# Macropad_V1_0.net
KiCad netlist of a schematic drawn in Altium Designer
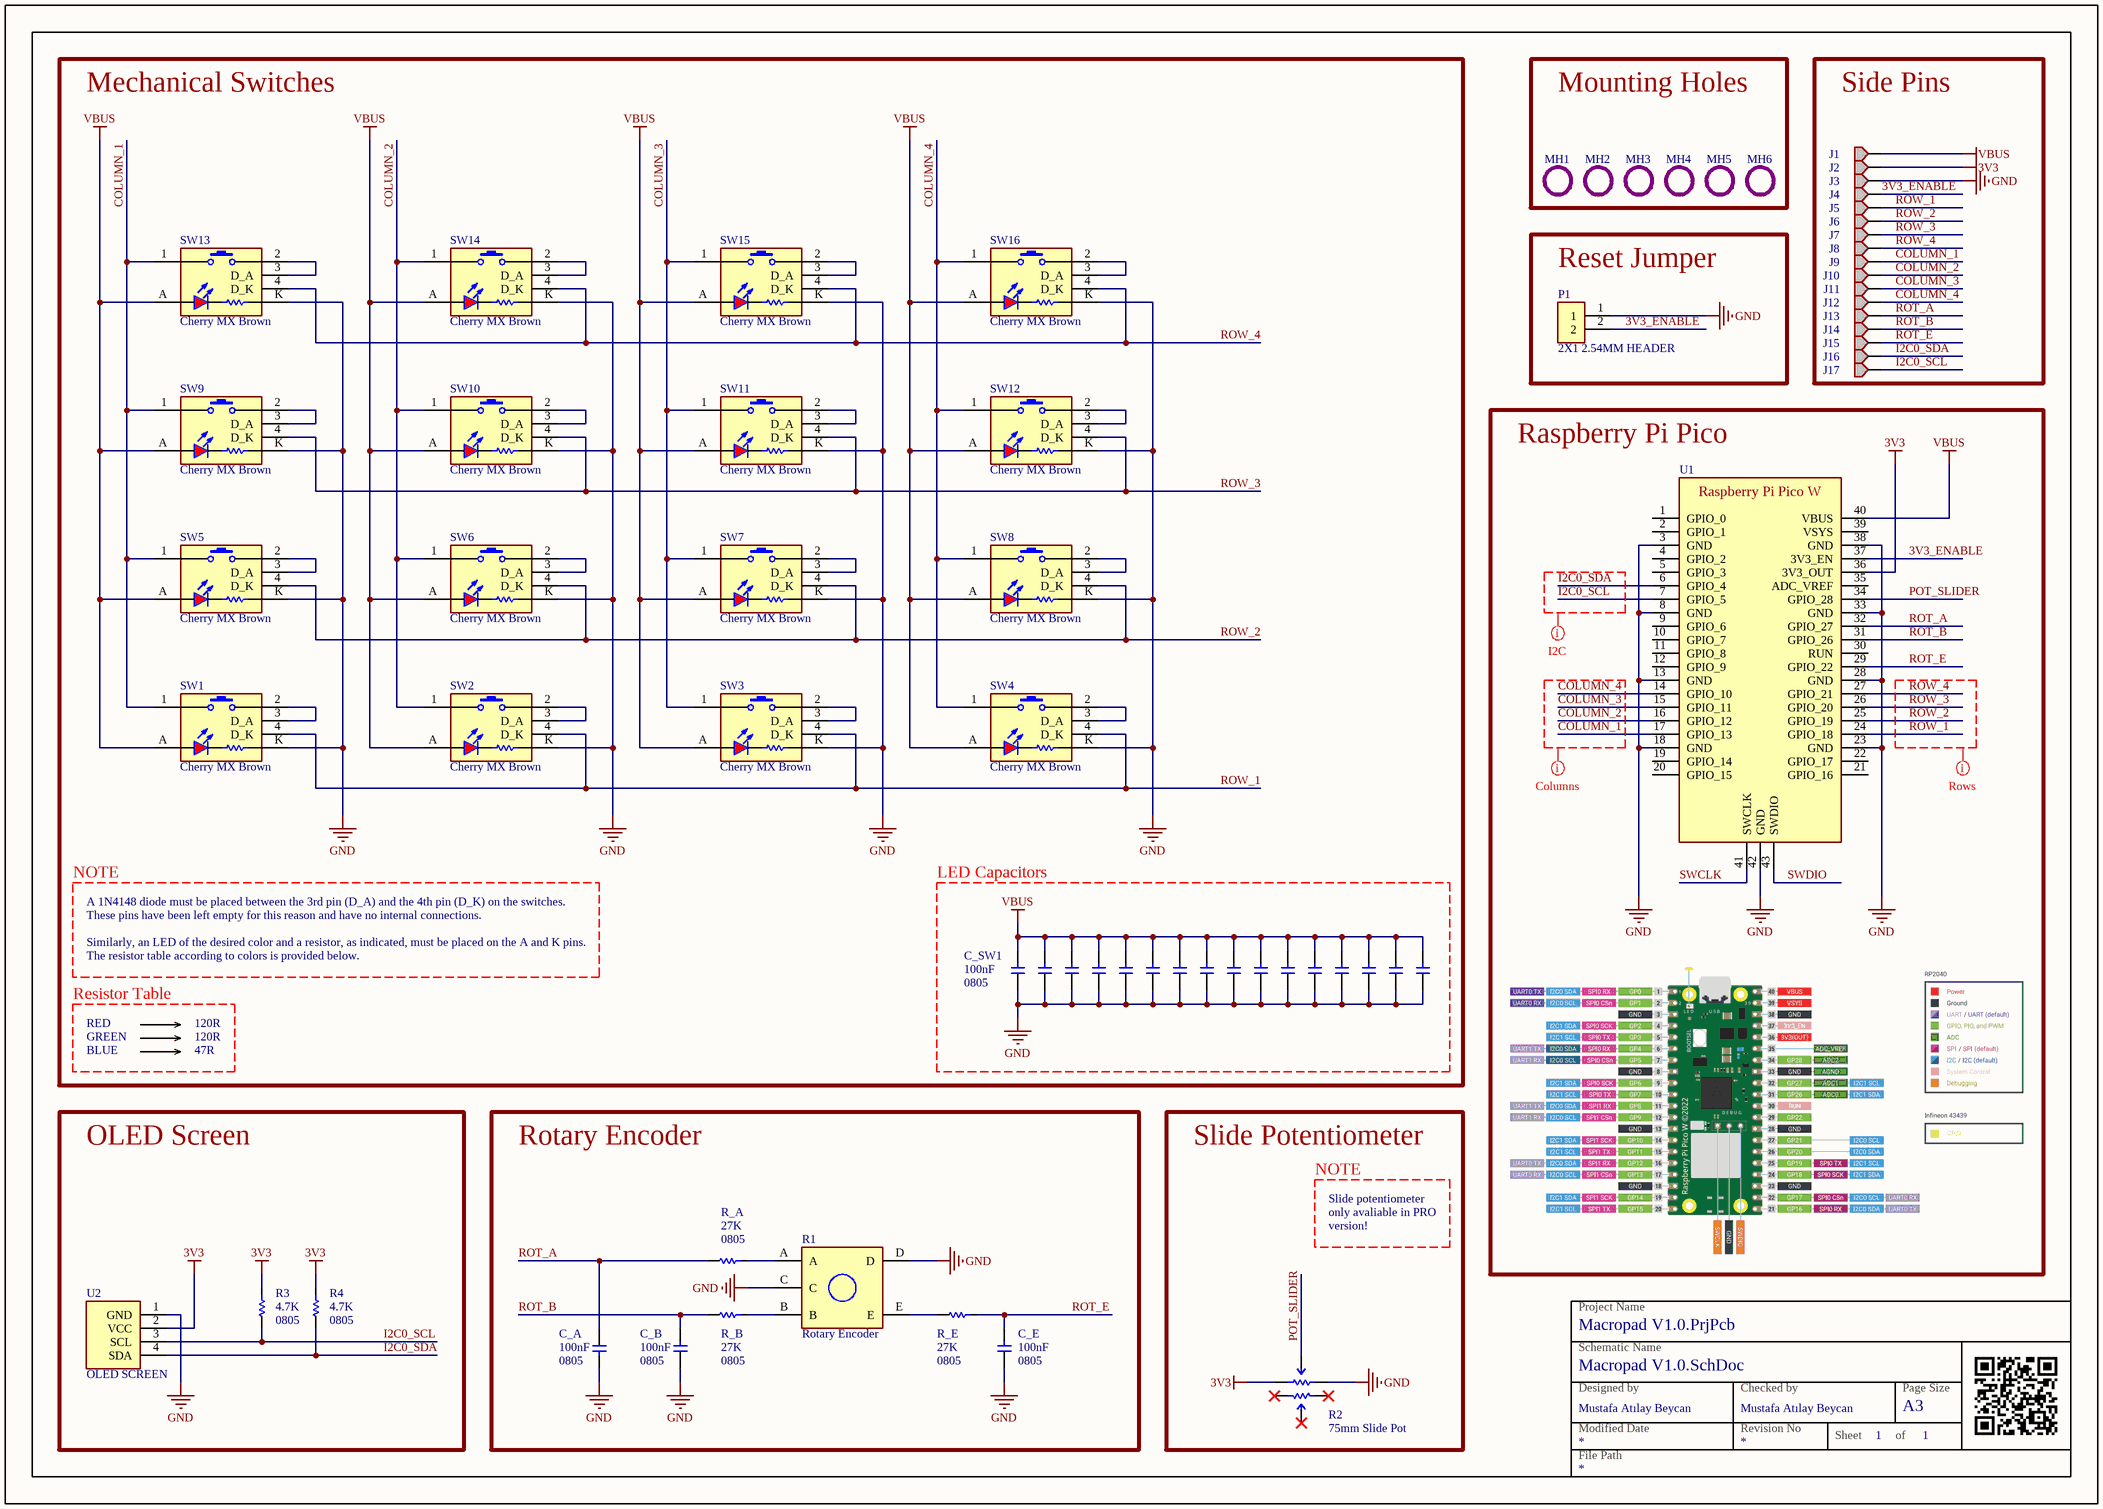
[diagram p0: Macropad V1.0.SchDoc]

(export (version "E")
  (design (tool "Eeschema 10.0.6"))
  (components
    (comp (ref "C_A")
      (value "CAP CER")
      (footprint "CAP 0805")
      (fields (field (name "CAPACITANCE") "100nF") (field (name "PACKAGE") "0805"))
      (libsource (lib "Mustafa Library") (part "CAP CER"))
    )
    (comp (ref "C_B")
      (value "CAP CER")
      (footprint "CAP 0805")
      (fields (field (name "CAPACITANCE") "100nF") (field (name "PACKAGE") "0805"))
      (libsource (lib "Mustafa Library") (part "CAP CER"))
    )
    (comp (ref "C_E")
      (value "CAP CER")
      (footprint "CAP 0805")
      (fields (field (name "CAPACITANCE") "100nF") (field (name "PACKAGE") "0805"))
      (libsource (lib "Mustafa Library") (part "CAP CER"))
    )
    (comp (ref "C_SW1")
      (value "CAP CER")
      (footprint "CAP 0805")
      (fields (field (name "CAPACITANCE") "100nF") (field (name "PACKAGE") "0805"))
      (libsource (lib "Mustafa Library") (part "CAP CER"))
    )
    (comp (ref "C_SW2")
      (value "CAP CER")
      (footprint "CAP 0805")
      (libsource (lib "Mustafa Library") (part "CAP CER"))
    )
    (comp (ref "C_SW3")
      (value "CAP CER")
      (footprint "CAP 0805")
      (libsource (lib "Mustafa Library") (part "CAP CER"))
    )
    (comp (ref "C_SW4")
      (value "CAP CER")
      (footprint "CAP 0805")
      (libsource (lib "Mustafa Library") (part "CAP CER"))
    )
    (comp (ref "C_SW5")
      (value "CAP CER")
      (footprint "CAP 0805")
      (libsource (lib "Mustafa Library") (part "CAP CER"))
    )
    (comp (ref "C_SW6")
      (value "CAP CER")
      (footprint "CAP 0805")
      (libsource (lib "Mustafa Library") (part "CAP CER"))
    )
    (comp (ref "C_SW7")
      (value "CAP CER")
      (footprint "CAP 0805")
      (libsource (lib "Mustafa Library") (part "CAP CER"))
    )
    (comp (ref "C_SW8")
      (value "CAP CER")
      (footprint "CAP 0805")
      (libsource (lib "Mustafa Library") (part "CAP CER"))
    )
    (comp (ref "C_SW9")
      (value "CAP CER")
      (footprint "CAP 0805")
      (libsource (lib "Mustafa Library") (part "CAP CER"))
    )
    (comp (ref "C_SW10")
      (value "CAP CER")
      (footprint "CAP 0805")
      (libsource (lib "Mustafa Library") (part "CAP CER"))
    )
    (comp (ref "C_SW11")
      (value "CAP CER")
      (footprint "CAP 0805")
      (libsource (lib "Mustafa Library") (part "CAP CER"))
    )
    (comp (ref "C_SW12")
      (value "CAP CER")
      (footprint "CAP 0805")
      (libsource (lib "Mustafa Library") (part "CAP CER"))
    )
    (comp (ref "C_SW13")
      (value "CAP CER")
      (footprint "CAP 0805")
      (libsource (lib "Mustafa Library") (part "CAP CER"))
    )
    (comp (ref "C_SW14")
      (value "CAP CER")
      (footprint "CAP 0805")
      (libsource (lib "Mustafa Library") (part "CAP CER"))
    )
    (comp (ref "C_SW15")
      (value "CAP CER")
      (footprint "CAP 0805")
      (libsource (lib "Mustafa Library") (part "CAP CER"))
    )
    (comp (ref "C_SW16")
      (value "CAP CER")
      (footprint "CAP 0805")
      (libsource (lib "Mustafa Library") (part "CAP CER"))
    )
    (comp (ref "J1")
      (value "PAD 1 PIN")
      (footprint "PAD 1 PIN")
      (libsource (lib "Mustafa Library") (part "PAD 1 PIN"))
    )
    (comp (ref "J2")
      (value "PAD 1 PIN")
      (footprint "PAD 1 PIN")
      (libsource (lib "Mustafa Library") (part "PAD 1 PIN"))
    )
    (comp (ref "J3")
      (value "PAD 1 PIN")
      (footprint "PAD 1 PIN")
      (libsource (lib "Mustafa Library") (part "PAD 1 PIN"))
    )
    (comp (ref "J4")
      (value "PAD 1 PIN")
      (footprint "PAD 1 PIN")
      (libsource (lib "Mustafa Library") (part "PAD 1 PIN"))
    )
    (comp (ref "J5")
      (value "PAD 1 PIN")
      (footprint "PAD 1 PIN")
      (libsource (lib "Mustafa Library") (part "PAD 1 PIN"))
    )
    (comp (ref "J6")
      (value "PAD 1 PIN")
      (footprint "PAD 1 PIN")
      (libsource (lib "Mustafa Library") (part "PAD 1 PIN"))
    )
    (comp (ref "J7")
      (value "PAD 1 PIN")
      (footprint "PAD 1 PIN")
      (libsource (lib "Mustafa Library") (part "PAD 1 PIN"))
    )
    (comp (ref "J8")
      (value "PAD 1 PIN")
      (footprint "PAD 1 PIN")
      (libsource (lib "Mustafa Library") (part "PAD 1 PIN"))
    )
    (comp (ref "J9")
      (value "PAD 1 PIN")
      (footprint "PAD 1 PIN")
      (libsource (lib "Mustafa Library") (part "PAD 1 PIN"))
    )
    (comp (ref "J10")
      (value "PAD 1 PIN")
      (footprint "PAD 1 PIN")
      (libsource (lib "Mustafa Library") (part "PAD 1 PIN"))
    )
    (comp (ref "J11")
      (value "PAD 1 PIN")
      (footprint "PAD 1 PIN")
      (libsource (lib "Mustafa Library") (part "PAD 1 PIN"))
    )
    (comp (ref "J12")
      (value "PAD 1 PIN")
      (footprint "PAD 1 PIN")
      (libsource (lib "Mustafa Library") (part "PAD 1 PIN"))
    )
    (comp (ref "J13")
      (value "PAD 1 PIN")
      (footprint "PAD 1 PIN")
      (libsource (lib "Mustafa Library") (part "PAD 1 PIN"))
    )
    (comp (ref "J14")
      (value "PAD 1 PIN")
      (footprint "PAD 1 PIN")
      (libsource (lib "Mustafa Library") (part "PAD 1 PIN"))
    )
    (comp (ref "J15")
      (value "PAD 1 PIN")
      (footprint "PAD 1 PIN")
      (libsource (lib "Mustafa Library") (part "PAD 1 PIN"))
    )
    (comp (ref "J16")
      (value "PAD 1 PIN")
      (footprint "PAD 1 PIN")
      (libsource (lib "Mustafa Library") (part "PAD 1 PIN"))
    )
    (comp (ref "J17")
      (value "PAD 1 PIN")
      (footprint "PAD 1 PIN")
      (libsource (lib "Mustafa Library") (part "PAD 1 PIN"))
    )
    (comp (ref "MH1")
      (value "MOUNTING HOLE")
      (footprint "MH 2.7MM")
      (libsource (lib "Mustafa Library") (part "MH"))
    )
    (comp (ref "MH2")
      (value "MOUNTING HOLE")
      (footprint "MH 2.7MM")
      (libsource (lib "Mustafa Library") (part "MH"))
    )
    (comp (ref "MH3")
      (value "MOUNTING HOLE")
      (footprint "MH 2.7MM")
      (libsource (lib "Mustafa Library") (part "MH"))
    )
    (comp (ref "MH4")
      (value "MOUNTING HOLE")
      (footprint "MH 2.7MM")
      (libsource (lib "Mustafa Library") (part "MH"))
    )
    (comp (ref "MH5")
      (value "MOUNTING HOLE")
      (footprint "MH 2.7MM")
      (libsource (lib "Mustafa Library") (part "MH"))
    )
    (comp (ref "MH6")
      (value "MOUNTING HOLE")
      (footprint "MH 2.7MM")
      (libsource (lib "Mustafa Library") (part "MH"))
    )
    (comp (ref "P1")
      (value "2X1 2.54MM HEADER")
      (footprint "HDR 2 PIN 2.54MM")
      (libsource (lib "Mustafa Library") (part "HDR - 2X1 2.54"))
    )
    (comp (ref "R1")
      (value "Rotary Encoder")
      (footprint "POT - ROTARY ENCODER")
      (libsource (lib "Mustafa Library") (part "POT - Rotary Encoder"))
    )
    (comp (ref "R2")
      (value "75mm Slide Pot")
      (footprint "POT - SLIDER 75MM")
      (libsource (lib "Mustafa Library") (part "POT - Slide Potentiometer Stereo"))
    )
    (comp (ref "R3")
      (value "RES CHIP")
      (footprint "RES 0805")
      (fields (field (name "RESISTANCE") "4.7K") (field (name "PACKAGE") "0805"))
      (libsource (lib "Mustafa Library") (part "RES CHIP"))
    )
    (comp (ref "R4")
      (value "RES CHIP")
      (footprint "RES 0805")
      (fields (field (name "RESISTANCE") "4.7K") (field (name "PACKAGE") "0805"))
      (libsource (lib "Mustafa Library") (part "RES CHIP"))
    )
    (comp (ref "R_A")
      (value "RES CHIP")
      (footprint "RES 0805")
      (fields (field (name "RESISTANCE") "27K") (field (name "PACKAGE") "0805"))
      (libsource (lib "Mustafa Library") (part "RES CHIP"))
    )
    (comp (ref "R_B")
      (value "RES CHIP")
      (footprint "RES 0805")
      (fields (field (name "RESISTANCE") "27K") (field (name "PACKAGE") "0805"))
      (libsource (lib "Mustafa Library") (part "RES CHIP"))
    )
    (comp (ref "R_E")
      (value "RES CHIP")
      (footprint "RES 0805")
      (fields (field (name "RESISTANCE") "27K") (field (name "PACKAGE") "0805"))
      (libsource (lib "Mustafa Library") (part "RES CHIP"))
    )
    (comp (ref "SW1")
      (value "Cherry MX Brown")
      (footprint "SW - CHERRY MX 1U")
      (description "MECHANICAL SWITCH CHERRY MX BROWN")
      (libsource (lib "Mustafa Library") (part "Cherry MX Brown"))
    )
    (comp (ref "SW2")
      (value "Cherry MX Brown")
      (footprint "SW - CHERRY MX 1U")
      (description "MECHANICAL SWITCH CHERRY MX BROWN")
      (libsource (lib "Mustafa Library") (part "Cherry MX Brown"))
    )
    (comp (ref "SW3")
      (value "Cherry MX Brown")
      (footprint "SW - CHERRY MX 1U")
      (description "MECHANICAL SWITCH CHERRY MX BROWN")
      (libsource (lib "Mustafa Library") (part "Cherry MX Brown"))
    )
    (comp (ref "SW4")
      (value "Cherry MX Brown")
      (footprint "SW - CHERRY MX 1U")
      (description "MECHANICAL SWITCH CHERRY MX BROWN")
      (libsource (lib "Mustafa Library") (part "Cherry MX Brown"))
    )
    (comp (ref "SW5")
      (value "Cherry MX Brown")
      (footprint "SW - CHERRY MX 1U")
      (description "MECHANICAL SWITCH CHERRY MX BROWN")
      (libsource (lib "Mustafa Library") (part "Cherry MX Brown"))
    )
    (comp (ref "SW6")
      (value "Cherry MX Brown")
      (footprint "SW - CHERRY MX 1U")
      (description "MECHANICAL SWITCH CHERRY MX BROWN")
      (libsource (lib "Mustafa Library") (part "Cherry MX Brown"))
    )
    (comp (ref "SW7")
      (value "Cherry MX Brown")
      (footprint "SW - CHERRY MX 1U")
      (description "MECHANICAL SWITCH CHERRY MX BROWN")
      (libsource (lib "Mustafa Library") (part "Cherry MX Brown"))
    )
    (comp (ref "SW8")
      (value "Cherry MX Brown")
      (footprint "SW - CHERRY MX 1U")
      (description "MECHANICAL SWITCH CHERRY MX BROWN")
      (libsource (lib "Mustafa Library") (part "Cherry MX Brown"))
    )
    (comp (ref "SW9")
      (value "Cherry MX Brown")
      (footprint "SW - CHERRY MX 1U")
      (description "MECHANICAL SWITCH CHERRY MX BROWN")
      (libsource (lib "Mustafa Library") (part "Cherry MX Brown"))
    )
    (comp (ref "SW10")
      (value "Cherry MX Brown")
      (footprint "SW - CHERRY MX 1U")
      (description "MECHANICAL SWITCH CHERRY MX BROWN")
      (libsource (lib "Mustafa Library") (part "Cherry MX Brown"))
    )
    (comp (ref "SW11")
      (value "Cherry MX Brown")
      (footprint "SW - CHERRY MX 1U")
      (description "MECHANICAL SWITCH CHERRY MX BROWN")
      (libsource (lib "Mustafa Library") (part "Cherry MX Brown"))
    )
    (comp (ref "SW12")
      (value "Cherry MX Brown")
      (footprint "SW - CHERRY MX 1U")
      (description "MECHANICAL SWITCH CHERRY MX BROWN")
      (libsource (lib "Mustafa Library") (part "Cherry MX Brown"))
    )
    (comp (ref "SW13")
      (value "Cherry MX Brown")
      (footprint "SW - CHERRY MX 1U")
      (description "MECHANICAL SWITCH CHERRY MX BROWN")
      (libsource (lib "Mustafa Library") (part "Cherry MX Brown"))
    )
    (comp (ref "SW14")
      (value "Cherry MX Brown")
      (footprint "SW - CHERRY MX 1U")
      (description "MECHANICAL SWITCH CHERRY MX BROWN")
      (libsource (lib "Mustafa Library") (part "Cherry MX Brown"))
    )
    (comp (ref "SW15")
      (value "Cherry MX Brown")
      (footprint "SW - CHERRY MX 1U")
      (description "MECHANICAL SWITCH CHERRY MX BROWN")
      (libsource (lib "Mustafa Library") (part "Cherry MX Brown"))
    )
    (comp (ref "SW16")
      (value "Cherry MX Brown")
      (footprint "SW - CHERRY MX 1U")
      (description "MECHANICAL SWITCH CHERRY MX BROWN")
      (libsource (lib "Mustafa Library") (part "Cherry MX Brown"))
    )
    (comp (ref "U1")
      (value "Raspberry Pi Pico W")
      (footprint "MOD - RP PICO W")
      (libsource (lib "Mustafa Library") (part "MOD - RP PICO W"))
    )
    (comp (ref "U2")
      (value "OLED SCREEN")
      (footprint "0.91 OLED")
      (description "0.91 OLED SCREEN I2C")
      (libsource (lib "Mustafa Library") (part "0.91 OLED"))
    )
  )
  (nets
    (net (code "1") (name "/3V3_ENABLE") (class "Default")
      (node (ref "J4") (pin "1") (pinfunction "1_1") (pintype "passive"))
      (node (ref "P1") (pin "2") (pinfunction "2_2") (pintype "passive"))
      (node (ref "U1") (pin "37") (pinfunction "3V3_EN_37") (pintype "passive"))
    )
    (net (code "2") (name "/COLUMN_1") (class "Default")
      (node (ref "J9") (pin "1") (pinfunction "1_1") (pintype "passive"))
      (node (ref "SW1") (pin "1") (pinfunction "S1_1") (pintype "passive"))
      (node (ref "SW13") (pin "1") (pinfunction "S1_1") (pintype "passive"))
      (node (ref "SW5") (pin "1") (pinfunction "S1_1") (pintype "passive"))
      (node (ref "SW9") (pin "1") (pinfunction "S1_1") (pintype "passive"))
      (node (ref "U1") (pin "17") (pinfunction "GPIO_13_17") (pintype "passive"))
    )
    (net (code "3") (name "/COLUMN_2") (class "Default")
      (node (ref "J10") (pin "1") (pinfunction "1_1") (pintype "passive"))
      (node (ref "SW10") (pin "1") (pinfunction "S1_1") (pintype "passive"))
      (node (ref "SW14") (pin "1") (pinfunction "S1_1") (pintype "passive"))
      (node (ref "SW2") (pin "1") (pinfunction "S1_1") (pintype "passive"))
      (node (ref "SW6") (pin "1") (pinfunction "S1_1") (pintype "passive"))
      (node (ref "U1") (pin "16") (pinfunction "GPIO_12_16") (pintype "passive"))
    )
    (net (code "4") (name "/COLUMN_3") (class "Default")
      (node (ref "J11") (pin "1") (pinfunction "1_1") (pintype "passive"))
      (node (ref "SW11") (pin "1") (pinfunction "S1_1") (pintype "passive"))
      (node (ref "SW15") (pin "1") (pinfunction "S1_1") (pintype "passive"))
      (node (ref "SW3") (pin "1") (pinfunction "S1_1") (pintype "passive"))
      (node (ref "SW7") (pin "1") (pinfunction "S1_1") (pintype "passive"))
      (node (ref "U1") (pin "15") (pinfunction "GPIO_11_15") (pintype "passive"))
    )
    (net (code "5") (name "/COLUMN_4") (class "Default")
      (node (ref "J12") (pin "1") (pinfunction "1_1") (pintype "passive"))
      (node (ref "SW12") (pin "1") (pinfunction "S1_1") (pintype "passive"))
      (node (ref "SW16") (pin "1") (pinfunction "S1_1") (pintype "passive"))
      (node (ref "SW4") (pin "1") (pinfunction "S1_1") (pintype "passive"))
      (node (ref "SW8") (pin "1") (pinfunction "S1_1") (pintype "passive"))
      (node (ref "U1") (pin "14") (pinfunction "GPIO_10_14") (pintype "passive"))
    )
    (net (code "6") (name "/I2C0_SCL") (class "Default")
      (node (ref "J17") (pin "1") (pinfunction "1_1") (pintype "passive"))
      (node (ref "R3") (pin "2") (pinfunction "2_2") (pintype "passive"))
      (node (ref "U1") (pin "7") (pinfunction "GPIO_5_7") (pintype "passive"))
      (node (ref "U2") (pin "3") (pinfunction "SCL_3") (pintype "passive"))
    )
    (net (code "7") (name "/I2C0_SDA") (class "Default")
      (node (ref "J16") (pin "1") (pinfunction "1_1") (pintype "passive"))
      (node (ref "R4") (pin "2") (pinfunction "2_2") (pintype "passive"))
      (node (ref "U1") (pin "6") (pinfunction "GPIO_4_6") (pintype "passive"))
      (node (ref "U2") (pin "4") (pinfunction "SDA_4") (pintype "passive"))
    )
    (net (code "8") (name "/POT_SLIDER") (class "Default")
      (node (ref "R2") (pin "2") (pinfunction "2_2") (pintype "passive"))
      (node (ref "U1") (pin "34") (pinfunction "GPIO_28_34") (pintype "passive"))
    )
    (net (code "9") (name "/ROT_A") (class "Default")
      (node (ref "C_A") (pin "2") (pinfunction "2_2") (pintype "passive"))
      (node (ref "J13") (pin "1") (pinfunction "1_1") (pintype "passive"))
      (node (ref "R_A") (pin "2") (pinfunction "2_2") (pintype "passive"))
      (node (ref "U1") (pin "32") (pinfunction "GPIO_27_32") (pintype "passive"))
    )
    (net (code "10") (name "/ROT_B") (class "Default")
      (node (ref "C_B") (pin "1") (pinfunction "1_1") (pintype "passive"))
      (node (ref "J14") (pin "1") (pinfunction "1_1") (pintype "passive"))
      (node (ref "R_B") (pin "2") (pinfunction "2_2") (pintype "passive"))
      (node (ref "U1") (pin "31") (pinfunction "GPIO_26_31") (pintype "passive"))
    )
    (net (code "11") (name "/ROT_E") (class "Default")
      (node (ref "C_E") (pin "1") (pinfunction "1_1") (pintype "passive"))
      (node (ref "J15") (pin "1") (pinfunction "1_1") (pintype "passive"))
      (node (ref "R_E") (pin "1") (pinfunction "1_1") (pintype "passive"))
      (node (ref "U1") (pin "29") (pinfunction "GPIO_22_29") (pintype "passive"))
    )
    (net (code "12") (name "/ROW_1") (class "Default")
      (node (ref "J5") (pin "1") (pinfunction "1_1") (pintype "passive"))
      (node (ref "SW1") (pin "4") (pinfunction "D_K_4") (pintype "passive"))
      (node (ref "SW2") (pin "4") (pinfunction "D_K_4") (pintype "passive"))
      (node (ref "SW3") (pin "4") (pinfunction "D_K_4") (pintype "passive"))
      (node (ref "SW4") (pin "4") (pinfunction "D_K_4") (pintype "passive"))
      (node (ref "U1") (pin "24") (pinfunction "GPIO_18_24") (pintype "passive"))
    )
    (net (code "13") (name "/ROW_2") (class "Default")
      (node (ref "J6") (pin "1") (pinfunction "1_1") (pintype "passive"))
      (node (ref "SW5") (pin "4") (pinfunction "D_K_4") (pintype "passive"))
      (node (ref "SW6") (pin "4") (pinfunction "D_K_4") (pintype "passive"))
      (node (ref "SW7") (pin "4") (pinfunction "D_K_4") (pintype "passive"))
      (node (ref "SW8") (pin "4") (pinfunction "D_K_4") (pintype "passive"))
      (node (ref "U1") (pin "25") (pinfunction "GPIO_19_25") (pintype "passive"))
    )
    (net (code "14") (name "/ROW_3") (class "Default")
      (node (ref "J7") (pin "1") (pinfunction "1_1") (pintype "passive"))
      (node (ref "SW10") (pin "4") (pinfunction "D_K_4") (pintype "passive"))
      (node (ref "SW11") (pin "4") (pinfunction "D_K_4") (pintype "passive"))
      (node (ref "SW12") (pin "4") (pinfunction "D_K_4") (pintype "passive"))
      (node (ref "SW9") (pin "4") (pinfunction "D_K_4") (pintype "passive"))
      (node (ref "U1") (pin "26") (pinfunction "GPIO_20_26") (pintype "passive"))
    )
    (net (code "15") (name "/ROW_4") (class "Default")
      (node (ref "J8") (pin "1") (pinfunction "1_1") (pintype "passive"))
      (node (ref "SW13") (pin "4") (pinfunction "D_K_4") (pintype "passive"))
      (node (ref "SW14") (pin "4") (pinfunction "D_K_4") (pintype "passive"))
      (node (ref "SW15") (pin "4") (pinfunction "D_K_4") (pintype "passive"))
      (node (ref "SW16") (pin "4") (pinfunction "D_K_4") (pintype "passive"))
      (node (ref "U1") (pin "27") (pinfunction "GPIO_21_27") (pintype "passive"))
    )
    (net (code "16") (name "/SWCLK") (class "Default")
      (node (ref "U1") (pin "41") (pinfunction "SWCLK_41") (pintype "passive"))
    )
    (net (code "17") (name "/SWDIO") (class "Default")
      (node (ref "U1") (pin "43") (pinfunction "SWDIO_43") (pintype "passive"))
    )
    (net (code "18") (name "3V3") (class "Default")
      (node (ref "J2") (pin "1") (pinfunction "1_1") (pintype "passive"))
      (node (ref "R2") (pin "1") (pinfunction "1_1") (pintype "passive"))
      (node (ref "R3") (pin "1") (pinfunction "1_1") (pintype "passive"))
      (node (ref "R4") (pin "1") (pinfunction "1_1") (pintype "passive"))
      (node (ref "U1") (pin "36") (pinfunction "3V3_OUT_36") (pintype "passive"))
      (node (ref "U2") (pin "2") (pinfunction "VCC_2") (pintype "passive"))
    )
    (net (code "19") (name "GND") (class "Default")
      (node (ref "C_A") (pin "1") (pinfunction "1_1") (pintype "passive"))
      (node (ref "C_B") (pin "2") (pinfunction "2_2") (pintype "passive"))
      (node (ref "C_E") (pin "2") (pinfunction "2_2") (pintype "passive"))
      (node (ref "C_SW1") (pin "2") (pinfunction "2_2") (pintype "passive"))
      (node (ref "C_SW10") (pin "2") (pinfunction "2_2") (pintype "passive"))
      (node (ref "C_SW11") (pin "2") (pinfunction "2_2") (pintype "passive"))
      (node (ref "C_SW12") (pin "2") (pinfunction "2_2") (pintype "passive"))
      (node (ref "C_SW13") (pin "2") (pinfunction "2_2") (pintype "passive"))
      (node (ref "C_SW14") (pin "2") (pinfunction "2_2") (pintype "passive"))
      (node (ref "C_SW15") (pin "2") (pinfunction "2_2") (pintype "passive"))
      (node (ref "C_SW16") (pin "2") (pinfunction "2_2") (pintype "passive"))
      (node (ref "C_SW2") (pin "2") (pinfunction "2_2") (pintype "passive"))
      (node (ref "C_SW3") (pin "2") (pinfunction "2_2") (pintype "passive"))
      (node (ref "C_SW4") (pin "2") (pinfunction "2_2") (pintype "passive"))
      (node (ref "C_SW5") (pin "2") (pinfunction "2_2") (pintype "passive"))
      (node (ref "C_SW6") (pin "2") (pinfunction "2_2") (pintype "passive"))
      (node (ref "C_SW7") (pin "2") (pinfunction "2_2") (pintype "passive"))
      (node (ref "C_SW8") (pin "2") (pinfunction "2_2") (pintype "passive"))
      (node (ref "C_SW9") (pin "2") (pinfunction "2_2") (pintype "passive"))
      (node (ref "J3") (pin "1") (pinfunction "1_1") (pintype "passive"))
      (node (ref "P1") (pin "1") (pinfunction "1_1") (pintype "passive"))
      (node (ref "R1") (pin "C") (pinfunction "C_C") (pintype "passive"))
      (node (ref "R1") (pin "D") (pinfunction "D_D") (pintype "passive"))
      (node (ref "R2") (pin "3") (pinfunction "3_3") (pintype "passive"))
      (node (ref "SW1") (pin "K") (pinfunction "6_K") (pintype "passive"))
      (node (ref "SW10") (pin "K") (pinfunction "6_K") (pintype "passive"))
      (node (ref "SW11") (pin "K") (pinfunction "6_K") (pintype "passive"))
      (node (ref "SW12") (pin "K") (pinfunction "6_K") (pintype "passive"))
      (node (ref "SW13") (pin "K") (pinfunction "6_K") (pintype "passive"))
      (node (ref "SW14") (pin "K") (pinfunction "6_K") (pintype "passive"))
      (node (ref "SW15") (pin "K") (pinfunction "6_K") (pintype "passive"))
      (node (ref "SW16") (pin "K") (pinfunction "6_K") (pintype "passive"))
      (node (ref "SW2") (pin "K") (pinfunction "6_K") (pintype "passive"))
      (node (ref "SW3") (pin "K") (pinfunction "6_K") (pintype "passive"))
      (node (ref "SW4") (pin "K") (pinfunction "6_K") (pintype "passive"))
      (node (ref "SW5") (pin "K") (pinfunction "6_K") (pintype "passive"))
      (node (ref "SW6") (pin "K") (pinfunction "6_K") (pintype "passive"))
      (node (ref "SW7") (pin "K") (pinfunction "6_K") (pintype "passive"))
      (node (ref "SW8") (pin "K") (pinfunction "6_K") (pintype "passive"))
      (node (ref "SW9") (pin "K") (pinfunction "6_K") (pintype "passive"))
      (node (ref "U1") (pin "13") (pinfunction "GND_13") (pintype "passive"))
      (node (ref "U1") (pin "18") (pinfunction "GND_18") (pintype "passive"))
      (node (ref "U1") (pin "23") (pinfunction "GND_23") (pintype "passive"))
      (node (ref "U1") (pin "28") (pinfunction "GND_28") (pintype "passive"))
      (node (ref "U1") (pin "3") (pinfunction "GND_3") (pintype "passive"))
      (node (ref "U1") (pin "33") (pinfunction "GND_33") (pintype "passive"))
      (node (ref "U1") (pin "38") (pinfunction "GND_38") (pintype "passive"))
      (node (ref "U1") (pin "42") (pinfunction "GND_42") (pintype "passive"))
      (node (ref "U1") (pin "8") (pinfunction "GND_8") (pintype "passive"))
      (node (ref "U2") (pin "1") (pinfunction "GND_1") (pintype "passive"))
    )
    (net (code "20") (name "Net-(R1-PadA)") (class "Default")
      (node (ref "R1") (pin "A") (pinfunction "A_A") (pintype "passive"))
      (node (ref "R_A") (pin "1") (pinfunction "1_1") (pintype "passive"))
    )
    (net (code "21") (name "Net-(R1-PadB)") (class "Default")
      (node (ref "R1") (pin "B") (pinfunction "B_B") (pintype "passive"))
      (node (ref "R_B") (pin "1") (pinfunction "1_1") (pintype "passive"))
    )
    (net (code "22") (name "Net-(R1-PadE)") (class "Default")
      (node (ref "R1") (pin "E") (pinfunction "E_E") (pintype "passive"))
      (node (ref "R_E") (pin "2") (pinfunction "2_2") (pintype "passive"))
    )
    (net (code "23") (name "Net-(SW1-D_A)") (class "Default")
      (node (ref "SW1") (pin "2") (pinfunction "S2_2") (pintype "passive"))
      (node (ref "SW1") (pin "3") (pinfunction "D_A_3") (pintype "passive"))
    )
    (net (code "24") (name "Net-(SW2-D_A)") (class "Default")
      (node (ref "SW2") (pin "2") (pinfunction "S2_2") (pintype "passive"))
      (node (ref "SW2") (pin "3") (pinfunction "D_A_3") (pintype "passive"))
    )
    (net (code "25") (name "Net-(SW3-D_A)") (class "Default")
      (node (ref "SW3") (pin "2") (pinfunction "S2_2") (pintype "passive"))
      (node (ref "SW3") (pin "3") (pinfunction "D_A_3") (pintype "passive"))
    )
    (net (code "26") (name "Net-(SW4-D_A)") (class "Default")
      (node (ref "SW4") (pin "2") (pinfunction "S2_2") (pintype "passive"))
      (node (ref "SW4") (pin "3") (pinfunction "D_A_3") (pintype "passive"))
    )
    (net (code "27") (name "Net-(SW5-D_A)") (class "Default")
      (node (ref "SW5") (pin "2") (pinfunction "S2_2") (pintype "passive"))
      (node (ref "SW5") (pin "3") (pinfunction "D_A_3") (pintype "passive"))
    )
    (net (code "28") (name "Net-(SW6-D_A)") (class "Default")
      (node (ref "SW6") (pin "2") (pinfunction "S2_2") (pintype "passive"))
      (node (ref "SW6") (pin "3") (pinfunction "D_A_3") (pintype "passive"))
    )
    (net (code "29") (name "Net-(SW7-D_A)") (class "Default")
      (node (ref "SW7") (pin "2") (pinfunction "S2_2") (pintype "passive"))
      (node (ref "SW7") (pin "3") (pinfunction "D_A_3") (pintype "passive"))
    )
    (net (code "30") (name "Net-(SW8-D_A)") (class "Default")
      (node (ref "SW8") (pin "2") (pinfunction "S2_2") (pintype "passive"))
      (node (ref "SW8") (pin "3") (pinfunction "D_A_3") (pintype "passive"))
    )
    (net (code "31") (name "Net-(SW9-D_A)") (class "Default")
      (node (ref "SW9") (pin "2") (pinfunction "S2_2") (pintype "passive"))
      (node (ref "SW9") (pin "3") (pinfunction "D_A_3") (pintype "passive"))
    )
    (net (code "32") (name "Net-(SW10-D_A)") (class "Default")
      (node (ref "SW10") (pin "2") (pinfunction "S2_2") (pintype "passive"))
      (node (ref "SW10") (pin "3") (pinfunction "D_A_3") (pintype "passive"))
    )
    (net (code "33") (name "Net-(SW11-D_A)") (class "Default")
      (node (ref "SW11") (pin "2") (pinfunction "S2_2") (pintype "passive"))
      (node (ref "SW11") (pin "3") (pinfunction "D_A_3") (pintype "passive"))
    )
    (net (code "34") (name "Net-(SW12-D_A)") (class "Default")
      (node (ref "SW12") (pin "2") (pinfunction "S2_2") (pintype "passive"))
      (node (ref "SW12") (pin "3") (pinfunction "D_A_3") (pintype "passive"))
    )
    (net (code "35") (name "Net-(SW13-D_A)") (class "Default")
      (node (ref "SW13") (pin "2") (pinfunction "S2_2") (pintype "passive"))
      (node (ref "SW13") (pin "3") (pinfunction "D_A_3") (pintype "passive"))
    )
    (net (code "36") (name "Net-(SW14-D_A)") (class "Default")
      (node (ref "SW14") (pin "2") (pinfunction "S2_2") (pintype "passive"))
      (node (ref "SW14") (pin "3") (pinfunction "D_A_3") (pintype "passive"))
    )
    (net (code "37") (name "Net-(SW15-D_A)") (class "Default")
      (node (ref "SW15") (pin "2") (pinfunction "S2_2") (pintype "passive"))
      (node (ref "SW15") (pin "3") (pinfunction "D_A_3") (pintype "passive"))
    )
    (net (code "38") (name "Net-(SW16-D_A)") (class "Default")
      (node (ref "SW16") (pin "2") (pinfunction "S2_2") (pintype "passive"))
      (node (ref "SW16") (pin "3") (pinfunction "D_A_3") (pintype "passive"))
    )
    (net (code "39") (name "VBUS") (class "Default")
      (node (ref "C_SW1") (pin "1") (pinfunction "1_1") (pintype "passive"))
      (node (ref "C_SW10") (pin "1") (pinfunction "1_1") (pintype "passive"))
      (node (ref "C_SW11") (pin "1") (pinfunction "1_1") (pintype "passive"))
      (node (ref "C_SW12") (pin "1") (pinfunction "1_1") (pintype "passive"))
      (node (ref "C_SW13") (pin "1") (pinfunction "1_1") (pintype "passive"))
      (node (ref "C_SW14") (pin "1") (pinfunction "1_1") (pintype "passive"))
      (node (ref "C_SW15") (pin "1") (pinfunction "1_1") (pintype "passive"))
      (node (ref "C_SW16") (pin "1") (pinfunction "1_1") (pintype "passive"))
      (node (ref "C_SW2") (pin "1") (pinfunction "1_1") (pintype "passive"))
      (node (ref "C_SW3") (pin "1") (pinfunction "1_1") (pintype "passive"))
      (node (ref "C_SW4") (pin "1") (pinfunction "1_1") (pintype "passive"))
      (node (ref "C_SW5") (pin "1") (pinfunction "1_1") (pintype "passive"))
      (node (ref "C_SW6") (pin "1") (pinfunction "1_1") (pintype "passive"))
      (node (ref "C_SW7") (pin "1") (pinfunction "1_1") (pintype "passive"))
      (node (ref "C_SW8") (pin "1") (pinfunction "1_1") (pintype "passive"))
      (node (ref "C_SW9") (pin "1") (pinfunction "1_1") (pintype "passive"))
      (node (ref "J1") (pin "1") (pinfunction "1_1") (pintype "passive"))
      (node (ref "SW1") (pin "A") (pinfunction "5_A") (pintype "passive"))
      (node (ref "SW10") (pin "A") (pinfunction "5_A") (pintype "passive"))
      (node (ref "SW11") (pin "A") (pinfunction "5_A") (pintype "passive"))
      (node (ref "SW12") (pin "A") (pinfunction "5_A") (pintype "passive"))
      (node (ref "SW13") (pin "A") (pinfunction "5_A") (pintype "passive"))
      (node (ref "SW14") (pin "A") (pinfunction "5_A") (pintype "passive"))
      (node (ref "SW15") (pin "A") (pinfunction "5_A") (pintype "passive"))
      (node (ref "SW16") (pin "A") (pinfunction "5_A") (pintype "passive"))
      (node (ref "SW2") (pin "A") (pinfunction "5_A") (pintype "passive"))
      (node (ref "SW3") (pin "A") (pinfunction "5_A") (pintype "passive"))
      (node (ref "SW4") (pin "A") (pinfunction "5_A") (pintype "passive"))
      (node (ref "SW5") (pin "A") (pinfunction "5_A") (pintype "passive"))
      (node (ref "SW6") (pin "A") (pinfunction "5_A") (pintype "passive"))
      (node (ref "SW7") (pin "A") (pinfunction "5_A") (pintype "passive"))
      (node (ref "SW8") (pin "A") (pinfunction "5_A") (pintype "passive"))
      (node (ref "SW9") (pin "A") (pinfunction "5_A") (pintype "passive"))
      (node (ref "U1") (pin "40") (pinfunction "VBUS_40") (pintype "passive"))
    )
    (net (code "40") (name "unconnected-(R2-Pad1')") (class "Default")
      (node (ref "R2") (pin "1'") (pinfunction "1'_1'") (pintype "passive+no_connect"))
    )
    (net (code "41") (name "unconnected-(R2-Pad2')") (class "Default")
      (node (ref "R2") (pin "2'") (pinfunction "2'_2'") (pintype "passive+no_connect"))
    )
    (net (code "42") (name "unconnected-(R2-Pad3')") (class "Default")
      (node (ref "R2") (pin "3'") (pinfunction "3'_3'") (pintype "passive+no_connect"))
    )
    (net (code "43") (name "unconnected-(U1-ADC_VREF-Pad35)") (class "Default")
      (node (ref "U1") (pin "35") (pinfunction "ADC_VREF_35") (pintype "passive"))
    )
    (net (code "44") (name "unconnected-(U1-GPIO_0-Pad1)") (class "Default")
      (node (ref "U1") (pin "1") (pinfunction "GPIO_0_1") (pintype "passive"))
    )
    (net (code "45") (name "unconnected-(U1-GPIO_1-Pad2)") (class "Default")
      (node (ref "U1") (pin "2") (pinfunction "GPIO_1_2") (pintype "passive"))
    )
    (net (code "46") (name "unconnected-(U1-GPIO_2-Pad4)") (class "Default")
      (node (ref "U1") (pin "4") (pinfunction "GPIO_2_4") (pintype "passive"))
    )
    (net (code "47") (name "unconnected-(U1-GPIO_3-Pad5)") (class "Default")
      (node (ref "U1") (pin "5") (pinfunction "GPIO_3_5") (pintype "passive"))
    )
    (net (code "48") (name "unconnected-(U1-GPIO_6-Pad9)") (class "Default")
      (node (ref "U1") (pin "9") (pinfunction "GPIO_6_9") (pintype "passive"))
    )
    (net (code "49") (name "unconnected-(U1-GPIO_7-Pad10)") (class "Default")
      (node (ref "U1") (pin "10") (pinfunction "GPIO_7_10") (pintype "passive"))
    )
    (net (code "50") (name "unconnected-(U1-GPIO_8-Pad11)") (class "Default")
      (node (ref "U1") (pin "11") (pinfunction "GPIO_8_11") (pintype "passive"))
    )
    (net (code "51") (name "unconnected-(U1-GPIO_9-Pad12)") (class "Default")
      (node (ref "U1") (pin "12") (pinfunction "GPIO_9_12") (pintype "passive"))
    )
    (net (code "52") (name "unconnected-(U1-GPIO_14-Pad19)") (class "Default")
      (node (ref "U1") (pin "19") (pinfunction "GPIO_14_19") (pintype "passive"))
    )
    (net (code "53") (name "unconnected-(U1-GPIO_15-Pad20)") (class "Default")
      (node (ref "U1") (pin "20") (pinfunction "GPIO_15_20") (pintype "passive"))
    )
    (net (code "54") (name "unconnected-(U1-GPIO_16-Pad21)") (class "Default")
      (node (ref "U1") (pin "21") (pinfunction "GPIO_16_21") (pintype "passive"))
    )
    (net (code "55") (name "unconnected-(U1-GPIO_17-Pad22)") (class "Default")
      (node (ref "U1") (pin "22") (pinfunction "GPIO_17_22") (pintype "passive"))
    )
    (net (code "56") (name "unconnected-(U1-RUN-Pad30)") (class "Default")
      (node (ref "U1") (pin "30") (pinfunction "RUN_30") (pintype "passive"))
    )
    (net (code "57") (name "unconnected-(U1-VSYS-Pad39)") (class "Default")
      (node (ref "U1") (pin "39") (pinfunction "VSYS_39") (pintype "passive"))
    )
  )
)
